# LEDMiniCube_PowerAndAnalog.net
KiCad netlist of a schematic drawn in Altium Designer
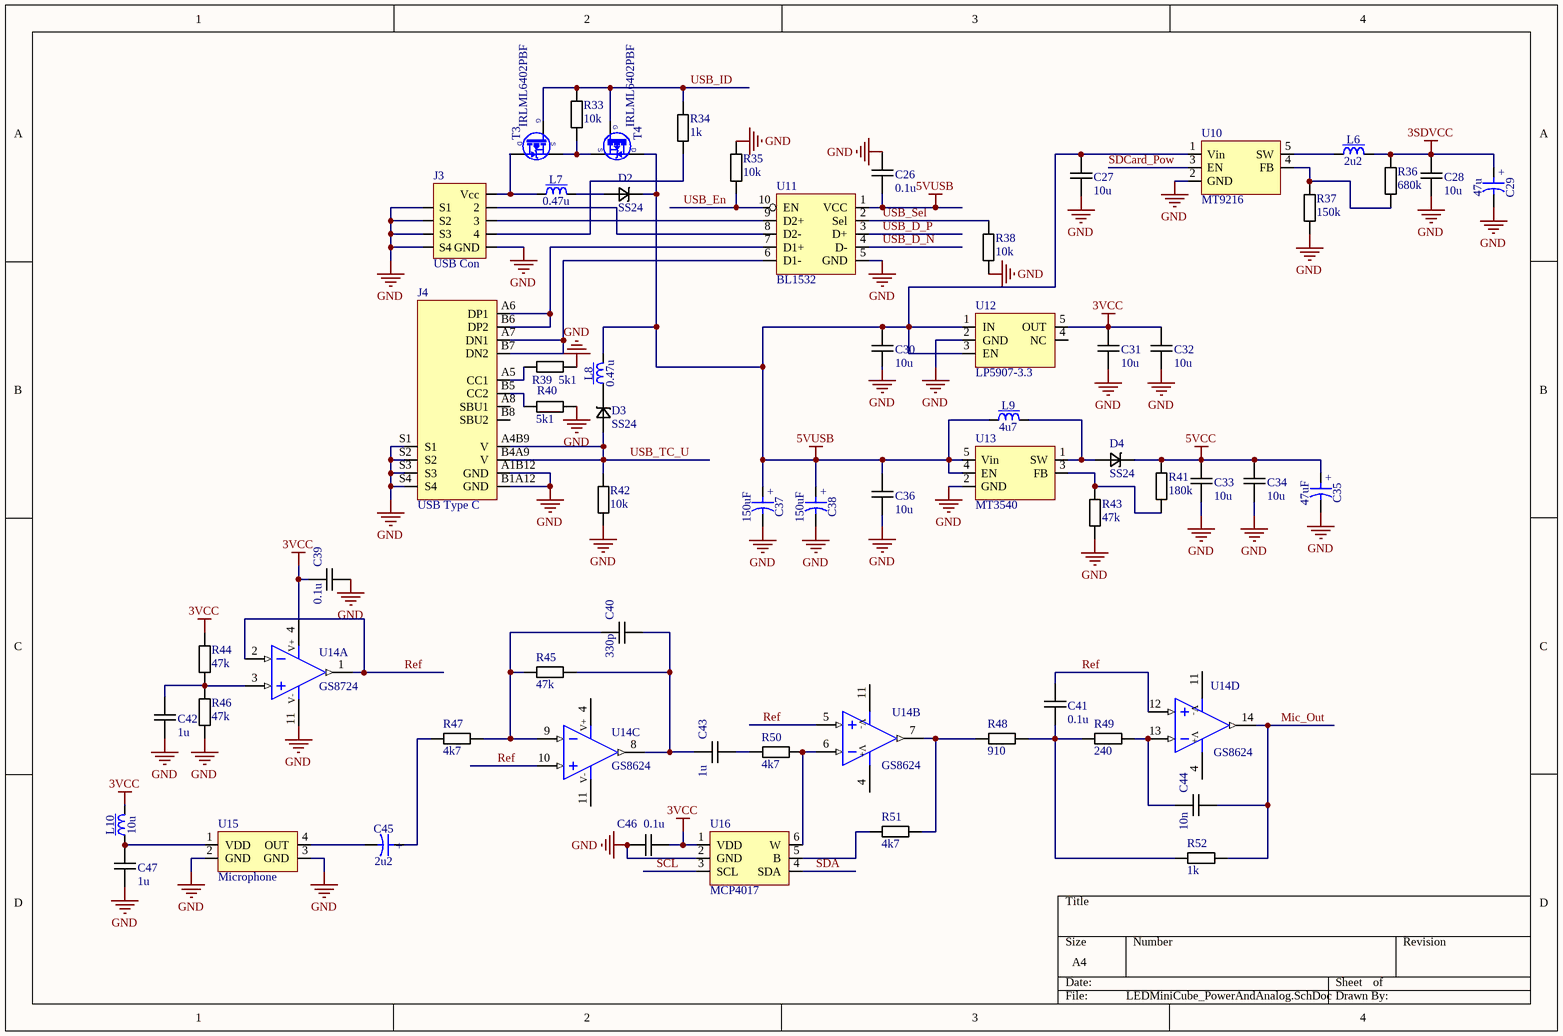
[diagram p0: LEDMiniCube_PowerAndAnalog.SchDoc]

(export (version "E")
  (design (tool "Eeschema 10.0.6"))
  (components
    (comp (ref "C26") (value "0.1u") (footprint "CAPC1608L") (libsource (lib "BMFT_lib") (part "Capacitor")))
    (comp (ref "C27") (value "10u") (footprint "CAPC2012L") (libsource (lib "BMFT_lib") (part "Capacitor")))
    (comp (ref "C28") (value "10u") (footprint "CAPC2012L") (libsource (lib "BMFT_lib") (part "Capacitor")))
    (comp (ref "C29")
      (value "47u")
      (footprint "CAPMP3216X180N")
      (description "Polarised capacitor")
      (fields
        (field (name "PART NUMBER") "CTE3216-18_100UF_6.3V_20%_ESR0500_AVX_TLJ")
        (field (name "VOLTAGE") "6.3V")
        (field (name "AUTHOR") "CERN DEM JLC")
      )
      (libsource (lib "Capacitors") (part "Capacitor - polarized"))
    )
    (comp (ref "C30") (value "10u") (footprint "CAPC2012L") (libsource (lib "BMFT_lib") (part "Capacitor")))
    (comp (ref "C31") (value "10u") (footprint "CAPC2012L") (libsource (lib "BMFT_lib") (part "Capacitor")))
    (comp (ref "C32") (value "10u") (footprint "CAPC2012L") (libsource (lib "BMFT_lib") (part "Capacitor")))
    (comp (ref "C33") (value "10u") (footprint "CAPC3216L") (libsource (lib "BMFT_lib") (part "Capacitor")))
    (comp (ref "C34") (value "10u") (footprint "CAPC3216L") (libsource (lib "BMFT_lib") (part "Capacitor")))
    (comp (ref "C35")
      (value "47uF")
      (footprint "CAPMP3528X120N")
      (description "Polarised capacitor")
      (fields (field (name "VOLTAGE") "10V") (field (name "AUTHOR") "CERN DEM JLC"))
      (libsource (lib "Capacitors") (part "Capacitor - polarized"))
    )
    (comp (ref "C36") (value "10u") (footprint "CAPC2012L") (libsource (lib "BMFT_lib") (part "Capacitor")))
    (comp (ref "C37")
      (value "150uF")
      (footprint "CAPMP7343X200N")
      (description "Polarised capacitor")
      (fields (field (name "VOLTAGE") "6.3V") (field (name "AUTHOR") "CERN DEM JLC"))
      (libsource (lib "Capacitors") (part "Capacitor - polarized"))
    )
    (comp (ref "C38")
      (value "150uF")
      (footprint "CAPMP7343X200N")
      (description "Polarised capacitor")
      (fields (field (name "VOLTAGE") "6.3V") (field (name "AUTHOR") "CERN DEM JLC"))
      (libsource (lib "Capacitors") (part "Capacitor - polarized"))
    )
    (comp (ref "C39") (value "0.1u") (footprint "CAPC1608L") (libsource (lib "BMFT_lib") (part "Capacitor")))
    (comp (ref "C40") (value "330p") (footprint "CAPC1608L") (libsource (lib "BMFT_lib") (part "Capacitor")))
    (comp (ref "C41") (value "0.1u") (footprint "CAPC1608L") (libsource (lib "BMFT_lib") (part "Capacitor")))
    (comp (ref "C42") (value "1u") (footprint "CAPC1608L") (libsource (lib "BMFT_lib") (part "Capacitor")))
    (comp (ref "C43") (value "1u") (footprint "CAPC2012L") (libsource (lib "BMFT_lib") (part "Capacitor")))
    (comp (ref "C44") (value "10n") (footprint "CAPC1608L") (libsource (lib "BMFT_lib") (part "Capacitor")))
    (comp (ref "C45")
      (value "2u2")
      (footprint "CAPMP3216X180N")
      (description "Polarised capacitor")
      (fields
        (field (name "PART NUMBER") "CTE3216-18_100UF_6.3V_20%_ESR0500_AVX_TLJ")
        (field (name "VOLTAGE") "6.3V")
        (field (name "AUTHOR") "CERN DEM JLC")
      )
      (libsource (lib "") (part "Capacitor - polarized_1"))
    )
    (comp (ref "C46") (value "0.1u") (footprint "CAPC1608L") (libsource (lib "BMFT_lib") (part "Capacitor")))
    (comp (ref "C47") (value "1u") (footprint "CAPC1608L") (libsource (lib "BMFT_lib") (part "Capacitor")))
    (comp (ref "D2") (value "SS24") (footprint "SOD-123F") (libsource (lib "BMFT_lib") (part "Schotky")))
    (comp (ref "D3") (value "SS24") (footprint "SOD-123F") (libsource (lib "BMFT_lib") (part "Schotky")))
    (comp (ref "D4") (value "SS24") (footprint "SOD-123F") (libsource (lib "BMFT_lib") (part "Schotky")))
    (comp (ref "J3") (value "USB Con") (footprint "ZX62D") (libsource (lib "BMFT_lib") (part "USB")))
    (comp (ref "J4")
      (value "USB Type C")
      (footprint "U262-161N-4BVC11")
      (fields (field (name "PART") "U262-161N-4BVC11"))
      (libsource (lib "DAC_lib") (part "USB_TypeC"))
    )
    (comp (ref "L6")
      (value "2u2")
      (footprint "IND_COILCRAFT_1206CS")
      (description "Inductor With Core")
      (fields (field (name "AUTHOR") "CERN DEM JLC"))
      (libsource (lib "") (part "Inductor With Magnetic core_1"))
    )
    (comp (ref "L7")
      (value "0.47u")
      (footprint "IND_COILCRAFT_0805CS")
      (description "Inductor With Core")
      (fields (field (name "AUTHOR") "CERN DEM JLC"))
      (libsource (lib "") (part "Inductor With Magnetic core_1"))
    )
    (comp (ref "L8")
      (value "0.47u")
      (footprint "IND_COILCRAFT_0805CS")
      (description "Inductor With Core")
      (fields (field (name "AUTHOR") "CERN DEM JLC"))
      (libsource (lib "Inductors & Transformers") (part "Inductor With Magnetic core"))
    )
    (comp (ref "L9")
      (value "4u7")
      (footprint "IND_COILCRAFT_1206CS")
      (description "Inductor With Core")
      (fields (field (name "AUTHOR") "CERN DEM JLC"))
      (libsource (lib "") (part "Inductor With Magnetic core_1"))
    )
    (comp (ref "L10")
      (value "10u")
      (footprint "INDC2012L")
      (description "Inductor With Core")
      (fields (field (name "AUTHOR") "CERN DEM JLC"))
      (libsource (lib "Inductors & Transformers") (part "Inductor With Magnetic core"))
    )
    (comp (ref "R33") (value "10k") (footprint "RESC1608L") (libsource (lib "BMFT_lib") (part "Resistor")))
    (comp (ref "R34") (value "1k") (footprint "RESC1608L") (libsource (lib "BMFT_lib") (part "Resistor")))
    (comp (ref "R35") (value "10k") (footprint "RESC1608L") (libsource (lib "BMFT_lib") (part "Resistor")))
    (comp (ref "R36") (value "680k") (footprint "RESC1608L") (libsource (lib "BMFT_lib") (part "Resistor")))
    (comp (ref "R37") (value "150k") (footprint "RESC1608L") (libsource (lib "BMFT_lib") (part "Resistor")))
    (comp (ref "R38") (value "10k") (footprint "RESC1608L") (libsource (lib "BMFT_lib") (part "Resistor")))
    (comp (ref "R39") (value "5k1") (footprint "RESC1608L") (libsource (lib "BMFT_lib") (part "Resistor")))
    (comp (ref "R40") (value "5k1") (footprint "RESC1608L") (libsource (lib "BMFT_lib") (part "Resistor")))
    (comp (ref "R41") (value "180k") (footprint "RESC1608L") (libsource (lib "BMFT_lib") (part "Resistor")))
    (comp (ref "R42") (value "10k") (footprint "RESC1608L") (libsource (lib "BMFT_lib") (part "Resistor")))
    (comp (ref "R43") (value "47k") (footprint "RESC1608L") (libsource (lib "BMFT_lib") (part "Resistor")))
    (comp (ref "R44") (value "47k") (footprint "RESC1608L") (libsource (lib "BMFT_lib") (part "Resistor")))
    (comp (ref "R45") (value "47k") (footprint "RESC1608L") (libsource (lib "BMFT_lib") (part "Resistor")))
    (comp (ref "R46") (value "47k") (footprint "RESC1608L") (libsource (lib "BMFT_lib") (part "Resistor")))
    (comp (ref "R47") (value "4k7") (footprint "RESC1608L") (libsource (lib "BMFT_lib") (part "Resistor")))
    (comp (ref "R48") (value "910") (footprint "RESC1608L") (libsource (lib "BMFT_lib") (part "Resistor")))
    (comp (ref "R49") (value "240") (footprint "RESC1608L") (libsource (lib "BMFT_lib") (part "Resistor")))
    (comp (ref "R50") (value "4k7") (footprint "RESC1608L") (libsource (lib "BMFT_lib") (part "Resistor")))
    (comp (ref "R51") (value "4k7") (footprint "RESC1608L") (libsource (lib "BMFT_lib") (part "Resistor")))
    (comp (ref "R52") (value "1k") (footprint "RESC1608L") (libsource (lib "BMFT_lib") (part "Resistor")))
    (comp (ref "T3")
      (value "IRLML6402PBF")
      (footprint "SOT95P237X112-3N")
      (description "P-CHANNEL MOSFET WITH ZENER DIODE")
      (fields (field (name "AUTHOR") "CERN DEM JLC"))
      (libsource (lib "ICs And Semiconductors") (part "P-MOSFET-DZ 1G 2S 3D"))
    )
    (comp (ref "T4")
      (value "IRLML6402PBF")
      (footprint "SOT95P237X112-3N")
      (description "P-CHANNEL MOSFET WITH ZENER DIODE")
      (fields (field (name "AUTHOR") "CERN DEM JLC"))
      (libsource (lib "") (part "P-MOSFET-DZ 1G 2S 3D_1"))
    )
    (comp (ref "U10") (value "MT9216") (footprint "SOT23-5AL") (libsource (lib "BMFT_lib") (part "LM3671")))
    (comp (ref "U11")
      (value "BL1532")
      (footprint "TSSOP50P490X110-10N")
      (libsource (lib "BMFT_lib") (part "BL1532"))
    )
    (comp (ref "U12")
      (value "LP5907-3.3")
      (footprint "SOT95P280X145-5M")
      (fields (field (name "PART") "LP5907MFX-3.3/NOPB"))
      (libsource (lib "DAC_lib") (part "TLV70233"))
    )
    (comp (ref "U13") (value "MT3540") (footprint "SOT23-5AL") (libsource (lib "BMFT_lib") (part "TPS6104x")))
    (comp (ref "U14")
      (value "GS8724")
      (footprint "SOP65P640X120-14N")
      (description "Quad Operational Amplifier")
      (fields (field (name "PART NUMBER") "GS8624-TR") (field (name "AUTHOR") "CERN DEM JLC"))
      (libsource (lib "ICs And Semiconductors") (part "Operational Amplifier x4 Type1"))
    )
    (comp (ref "U15")
      (value "Microphone")
      (footprint "Microphone 3.76x2.95")
      (libsource (lib "BMFT_lib") (part "Microphone MEMS"))
    )
    (comp (ref "U16")
      (value "MCP4017")
      (footprint "SOT65P210X110-6M")
      (libsource (lib "BMFT_lib") (part "MCP4017"))
    )
  )
  (nets
    (net (code "1") (name "/Mic_Out") (class "Default")
      (node (ref "C44") (pin "2") (pintype "passive"))
      (node (ref "R52") (pin "2") (pintype "passive"))
      (node (ref "U14") (pin "14") (pinfunction "OUT_14") (pintype "output"))
    )
    (net (code "2") (name "/Ref") (class "Default")
      (node (ref "C41") (pin "2") (pintype "passive"))
      (node (ref "U14") (pin "1") (pinfunction "OUT_1") (pintype "output"))
      (node (ref "U14") (pin "10") (pinfunction "IN+_10") (pintype "input"))
      (node (ref "U14") (pin "12") (pinfunction "IN+_12") (pintype "input"))
      (node (ref "U14") (pin "2") (pinfunction "IN-_2") (pintype "input"))
      (node (ref "U14") (pin "5") (pinfunction "IN+_5") (pintype "input"))
    )
    (net (code "3") (name "/SCL") (class "Default")
      (node (ref "U16") (pin "3") (pinfunction "SCL_3") (pintype "passive"))
    )
    (net (code "4") (name "/SDA") (class "Default")
      (node (ref "U16") (pin "4") (pinfunction "SDA_4") (pintype "passive"))
    )
    (net (code "5") (name "/SDCard_Pow") (class "Default")
      (node (ref "U10") (pin "3") (pinfunction "EN_3") (pintype "passive"))
    )
    (net (code "6") (name "/USB_D_N") (class "Default")
      (node (ref "U11") (pin "4") (pinfunction "D-_4") (pintype "passive"))
    )
    (net (code "7") (name "/USB_D_P") (class "Default")
      (node (ref "U11") (pin "3") (pinfunction "D+_3") (pintype "passive"))
    )
    (net (code "8") (name "/USB_En") (class "Default")
      (node (ref "R35") (pin "1") (pintype "passive"))
      (node (ref "U11") (pin "10") (pinfunction "EN_10") (pintype "passive"))
    )
    (net (code "9") (name "/USB_ID") (class "Default")
      (node (ref "R33") (pin "2") (pintype "passive"))
      (node (ref "R34") (pin "2") (pintype "passive"))
      (node (ref "T3") (pin "1") (pinfunction "G_1") (pintype "passive"))
      (node (ref "T4") (pin "1") (pinfunction "G_1") (pintype "passive"))
    )
    (net (code "10") (name "/USB_Sel") (class "Default")
      (node (ref "R38") (pin "2") (pintype "passive"))
      (node (ref "U11") (pin "2") (pinfunction "Sel_2") (pintype "passive"))
    )
    (net (code "11") (name "/USB_TC_U") (class "Default")
      (node (ref "D3") (pin "1") (pintype "passive"))
      (node (ref "J4") (pin "A4B9") (pinfunction "V_A4B9") (pintype "passive"))
      (node (ref "J4") (pin "B4A9") (pinfunction "V_B4A9") (pintype "passive"))
      (node (ref "R42") (pin "2") (pintype "passive"))
    )
    (net (code "12") (name "3SDVCC") (class "Default")
      (node (ref "C28") (pin "2") (pintype "passive"))
      (node (ref "C29") (pin "1") (pinfunction "1_1") (pintype "passive"))
      (node (ref "L6") (pin "2") (pinfunction "2_2") (pintype "passive"))
      (node (ref "R36") (pin "2") (pintype "passive"))
    )
    (net (code "13") (name "3VCC") (class "Default")
      (node (ref "C31") (pin "2") (pintype "passive"))
      (node (ref "C32") (pin "2") (pintype "passive"))
      (node (ref "C39") (pin "1") (pintype "passive"))
      (node (ref "C46") (pin "2") (pintype "passive"))
      (node (ref "L10") (pin "2") (pinfunction "2_2") (pintype "passive"))
      (node (ref "R44") (pin "2") (pintype "passive"))
      (node (ref "U12") (pin "5") (pinfunction "OUT_5") (pintype "passive"))
      (node (ref "U14") (pin "4") (pinfunction "V+_4") (pintype "power_in"))
      (node (ref "U16") (pin "1") (pinfunction "VDD_1") (pintype "passive"))
    )
    (net (code "14") (name "5VCC") (class "Default")
      (node (ref "C33") (pin "2") (pintype "passive"))
      (node (ref "C34") (pin "2") (pintype "passive"))
      (node (ref "C35") (pin "1") (pinfunction "1_1") (pintype "passive"))
      (node (ref "D4") (pin "2") (pintype "passive"))
      (node (ref "R41") (pin "2") (pintype "passive"))
    )
    (net (code "15") (name "5VUSB") (class "Default")
      (node (ref "C26") (pin "1") (pintype "passive"))
      (node (ref "C27") (pin "2") (pintype "passive"))
      (node (ref "C30") (pin "2") (pintype "passive"))
      (node (ref "C36") (pin "2") (pintype "passive"))
      (node (ref "C37") (pin "1") (pinfunction "1_1") (pintype "passive"))
      (node (ref "C38") (pin "1") (pinfunction "1_1") (pintype "passive"))
      (node (ref "D2") (pin "2") (pintype "passive"))
      (node (ref "L8") (pin "2") (pinfunction "2_2") (pintype "passive"))
      (node (ref "L9") (pin "1") (pinfunction "1_1") (pintype "passive"))
      (node (ref "T4") (pin "3") (pinfunction "D_3") (pintype "passive"))
      (node (ref "U10") (pin "1") (pinfunction "Vin_1") (pintype "power_in"))
      (node (ref "U11") (pin "1") (pinfunction "VCC_1") (pintype "passive"))
      (node (ref "U12") (pin "1") (pinfunction "IN_1") (pintype "passive"))
      (node (ref "U12") (pin "3") (pinfunction "EN_3") (pintype "passive"))
      (node (ref "U13") (pin "4") (pinfunction "EN_4") (pintype "passive"))
      (node (ref "U13") (pin "5") (pinfunction "Vin_5") (pintype "power_in"))
    )
    (net (code "16") (name "GND") (class "Default")
      (node (ref "C26") (pin "2") (pintype "passive"))
      (node (ref "C27") (pin "1") (pintype "passive"))
      (node (ref "C28") (pin "1") (pintype "passive"))
      (node (ref "C29") (pin "2") (pinfunction "2_2") (pintype "passive"))
      (node (ref "C30") (pin "1") (pintype "passive"))
      (node (ref "C31") (pin "1") (pintype "passive"))
      (node (ref "C32") (pin "1") (pintype "passive"))
      (node (ref "C33") (pin "1") (pintype "passive"))
      (node (ref "C34") (pin "1") (pintype "passive"))
      (node (ref "C35") (pin "2") (pinfunction "2_2") (pintype "passive"))
      (node (ref "C36") (pin "1") (pintype "passive"))
      (node (ref "C37") (pin "2") (pinfunction "2_2") (pintype "passive"))
      (node (ref "C38") (pin "2") (pinfunction "2_2") (pintype "passive"))
      (node (ref "C39") (pin "2") (pintype "passive"))
      (node (ref "C42") (pin "1") (pintype "passive"))
      (node (ref "C46") (pin "1") (pintype "passive"))
      (node (ref "C47") (pin "1") (pintype "passive"))
      (node (ref "J3") (pin "5") (pinfunction "GND_5") (pintype "power_in"))
      (node (ref "J3") (pin "S1") (pinfunction "S1_S1") (pintype "passive"))
      (node (ref "J3") (pin "S2") (pinfunction "S2_S2") (pintype "passive"))
      (node (ref "J3") (pin "S3") (pinfunction "S3_S3") (pintype "passive"))
      (node (ref "J3") (pin "S4") (pinfunction "S4_S4") (pintype "passive"))
      (node (ref "J4") (pin "A1B12") (pinfunction "GND_A1B12") (pintype "passive"))
      (node (ref "J4") (pin "B1A12") (pinfunction "GND_B1A12") (pintype "passive"))
      (node (ref "J4") (pin "S1") (pinfunction "S1_S1") (pintype "passive"))
      (node (ref "J4") (pin "S2") (pinfunction "S2_S2") (pintype "passive"))
      (node (ref "J4") (pin "S3") (pinfunction "S3_S3") (pintype "passive"))
      (node (ref "J4") (pin "S4") (pinfunction "S4_S4") (pintype "passive"))
      (node (ref "R35") (pin "2") (pintype "passive"))
      (node (ref "R37") (pin "1") (pintype "passive"))
      (node (ref "R38") (pin "1") (pintype "passive"))
      (node (ref "R39") (pin "2") (pintype "passive"))
      (node (ref "R40") (pin "2") (pintype "passive"))
      (node (ref "R42") (pin "1") (pintype "passive"))
      (node (ref "R43") (pin "1") (pintype "passive"))
      (node (ref "R46") (pin "1") (pintype "passive"))
      (node (ref "U10") (pin "2") (pinfunction "GND_2") (pintype "power_in"))
      (node (ref "U11") (pin "5") (pinfunction "GND_5") (pintype "passive"))
      (node (ref "U12") (pin "2") (pinfunction "GND_2") (pintype "passive"))
      (node (ref "U13") (pin "2") (pinfunction "GND_2") (pintype "power_in"))
      (node (ref "U14") (pin "11") (pinfunction "V-_11") (pintype "power_in"))
      (node (ref "U15") (pin "2") (pinfunction "GND_2") (pintype "passive"))
      (node (ref "U15") (pin "3") (pinfunction "GND_3") (pintype "passive"))
      (node (ref "U16") (pin "2") (pinfunction "GND_2") (pintype "passive"))
    )
    (net (code "17") (name "Net-(C41-Pad1)") (class "Default")
      (node (ref "C41") (pin "1") (pintype "passive"))
      (node (ref "R48") (pin "2") (pintype "passive"))
      (node (ref "R49") (pin "1") (pintype "passive"))
      (node (ref "R52") (pin "1") (pintype "passive"))
    )
    (net (code "18") (name "Net-(C43-Pad2)") (class "Default")
      (node (ref "C43") (pin "2") (pintype "passive"))
      (node (ref "R50") (pin "1") (pintype "passive"))
    )
    (net (code "19") (name "Net-(C45-Pad1)") (class "Default")
      (node (ref "C45") (pin "1") (pinfunction "1_1") (pintype "passive"))
      (node (ref "R47") (pin "1") (pintype "passive"))
    )
    (net (code "20") (name "Net-(D2-Pad1)") (class "Default")
      (node (ref "D2") (pin "1") (pintype "passive"))
      (node (ref "L7") (pin "2") (pinfunction "2_2") (pintype "passive"))
    )
    (net (code "21") (name "Net-(D3-Pad2)") (class "Default")
      (node (ref "D3") (pin "2") (pintype "passive"))
      (node (ref "L8") (pin "1") (pinfunction "1_1") (pintype "passive"))
    )
    (net (code "22") (name "Net-(J3-Pad4)") (class "Default")
      (node (ref "J3") (pin "4") (pinfunction "4_4") (pintype "passive"))
      (node (ref "R34") (pin "1") (pintype "passive"))
    )
    (net (code "23") (name "Net-(J3-Vcc)") (class "Default")
      (node (ref "J3") (pin "1") (pinfunction "Vcc_1") (pintype "power_in"))
      (node (ref "L7") (pin "1") (pinfunction "1_1") (pintype "passive"))
      (node (ref "T3") (pin "3") (pinfunction "D_3") (pintype "passive"))
    )
    (net (code "24") (name "Net-(J4-CC1)") (class "Default")
      (node (ref "J4") (pin "A5") (pinfunction "CC1_A5") (pintype "passive"))
      (node (ref "R39") (pin "1") (pintype "passive"))
    )
    (net (code "25") (name "Net-(J4-CC2)") (class "Default")
      (node (ref "J4") (pin "B5") (pinfunction "CC2_B5") (pintype "passive"))
      (node (ref "R40") (pin "1") (pintype "passive"))
    )
    (net (code "26") (name "Net-(J4-DN1)") (class "Default")
      (node (ref "J4") (pin "A7") (pinfunction "DN1_A7") (pintype "passive"))
      (node (ref "J4") (pin "B7") (pinfunction "DN2_B7") (pintype "passive"))
      (node (ref "U11") (pin "6") (pinfunction "D1-_6") (pintype "passive"))
    )
    (net (code "27") (name "Net-(J4-DP1)") (class "Default")
      (node (ref "J4") (pin "A6") (pinfunction "DP1_A6") (pintype "passive"))
      (node (ref "J4") (pin "B6") (pinfunction "DP2_B6") (pintype "passive"))
      (node (ref "U11") (pin "7") (pinfunction "D1+_7") (pintype "passive"))
    )
    (net (code "28") (name "Net-(T3-S)") (class "Default")
      (node (ref "R33") (pin "1") (pintype "passive"))
      (node (ref "T3") (pin "2") (pinfunction "S_2") (pintype "passive"))
      (node (ref "T4") (pin "2") (pinfunction "S_2") (pintype "passive"))
    )
    (net (code "29") (name "Net-(U10-FB)") (class "Default")
      (node (ref "R36") (pin "1") (pintype "passive"))
      (node (ref "R37") (pin "2") (pintype "passive"))
      (node (ref "U10") (pin "4") (pinfunction "FB_4") (pintype "passive"))
    )
    (net (code "30") (name "Net-(U10-SW)") (class "Default")
      (node (ref "L6") (pin "1") (pinfunction "1_1") (pintype "passive"))
      (node (ref "U10") (pin "5") (pinfunction "SW_5") (pintype "power_in"))
    )
    (net (code "31") (name "Net-(U11-D2+)") (class "Default")
      (node (ref "J3") (pin "3") (pinfunction "3_3") (pintype "passive"))
      (node (ref "U11") (pin "9") (pinfunction "D2+_9") (pintype "passive"))
    )
    (net (code "32") (name "Net-(U11-D2-)") (class "Default")
      (node (ref "J3") (pin "2") (pinfunction "2_2") (pintype "passive"))
      (node (ref "U11") (pin "8") (pinfunction "D2-_8") (pintype "passive"))
    )
    (net (code "33") (name "Net-(U13-FB)") (class "Default")
      (node (ref "R41") (pin "1") (pintype "passive"))
      (node (ref "R43") (pin "2") (pintype "passive"))
      (node (ref "U13") (pin "3") (pinfunction "FB_3") (pintype "passive"))
    )
    (net (code "34") (name "Net-(U13-SW)") (class "Default")
      (node (ref "D4") (pin "1") (pintype "passive"))
      (node (ref "L9") (pin "2") (pinfunction "2_2") (pintype "passive"))
      (node (ref "U13") (pin "1") (pinfunction "SW_1") (pintype "power_in"))
    )
    (net (code "35") (name "Net-(U14A-IN+)") (class "Default")
      (node (ref "C42") (pin "2") (pintype "passive"))
      (node (ref "R44") (pin "1") (pintype "passive"))
      (node (ref "R46") (pin "2") (pintype "passive"))
      (node (ref "U14") (pin "3") (pinfunction "IN+_3") (pintype "input"))
    )
    (net (code "36") (name "Net-(U14B-IN-)") (class "Default")
      (node (ref "R50") (pin "2") (pintype "passive"))
      (node (ref "U14") (pin "6") (pinfunction "IN-_6") (pintype "input"))
      (node (ref "U16") (pin "6") (pinfunction "W_6") (pintype "passive"))
    )
    (net (code "37") (name "Net-(U14B-OUT)") (class "Default")
      (node (ref "R48") (pin "1") (pintype "passive"))
      (node (ref "R51") (pin "2") (pintype "passive"))
      (node (ref "U14") (pin "7") (pinfunction "OUT_7") (pintype "output"))
    )
    (net (code "38") (name "Net-(U14C-IN-)") (class "Default")
      (node (ref "C40") (pin "1") (pintype "passive"))
      (node (ref "R45") (pin "1") (pintype "passive"))
      (node (ref "R47") (pin "2") (pintype "passive"))
      (node (ref "U14") (pin "9") (pinfunction "IN-_9") (pintype "input"))
    )
    (net (code "39") (name "Net-(U14C-OUT)") (class "Default")
      (node (ref "C40") (pin "2") (pintype "passive"))
      (node (ref "C43") (pin "1") (pintype "passive"))
      (node (ref "R45") (pin "2") (pintype "passive"))
      (node (ref "U14") (pin "8") (pinfunction "OUT_8") (pintype "output"))
    )
    (net (code "40") (name "Net-(U14D-IN-)") (class "Default")
      (node (ref "C44") (pin "1") (pintype "passive"))
      (node (ref "R49") (pin "2") (pintype "passive"))
      (node (ref "U14") (pin "13") (pinfunction "IN-_13") (pintype "input"))
    )
    (net (code "41") (name "Net-(U15-OUT)") (class "Default")
      (node (ref "C45") (pin "2") (pinfunction "2_2") (pintype "passive"))
      (node (ref "U15") (pin "4") (pinfunction "OUT_4") (pintype "passive"))
    )
    (net (code "42") (name "Net-(U15-VDD)") (class "Default")
      (node (ref "C47") (pin "2") (pintype "passive"))
      (node (ref "L10") (pin "1") (pinfunction "1_1") (pintype "passive"))
      (node (ref "U15") (pin "1") (pinfunction "VDD_1") (pintype "passive"))
    )
    (net (code "43") (name "Net-(U16-B)") (class "Default")
      (node (ref "R51") (pin "1") (pintype "passive"))
      (node (ref "U16") (pin "5") (pinfunction "B_5") (pintype "passive"))
    )
    (net (code "44") (name "unconnected-(J4-SBU1-PadA8)") (class "Default")
      (node (ref "J4") (pin "A8") (pinfunction "SBU1_A8") (pintype "passive"))
    )
    (net (code "45") (name "unconnected-(J4-SBU2-PadB8)") (class "Default")
      (node (ref "J4") (pin "B8") (pinfunction "SBU2_B8") (pintype "passive"))
    )
    (net (code "46") (name "unconnected-(U12-NC-Pad4)") (class "Default")
      (node (ref "U12") (pin "4") (pinfunction "NC_4") (pintype "passive"))
    )
    (net (code "47") (name "unconnected-(U14B-V+-Pad4)") (class "Default")
      (node (ref "U14") (pin "4") (pinfunction "V+_4") (pintype "power_in"))
    )
    (net (code "48") (name "unconnected-(U14B-V--Pad11)") (class "Default")
      (node (ref "U14") (pin "11") (pinfunction "V-_11") (pintype "power_in"))
    )
    (net (code "49") (name "unconnected-(U14C-V+-Pad4)") (class "Default")
      (node (ref "U14") (pin "4") (pinfunction "V+_4") (pintype "power_in"))
    )
    (net (code "50") (name "unconnected-(U14C-V--Pad11)") (class "Default")
      (node (ref "U14") (pin "11") (pinfunction "V-_11") (pintype "power_in"))
    )
    (net (code "51") (name "unconnected-(U14D-V+-Pad4)") (class "Default")
      (node (ref "U14") (pin "4") (pinfunction "V+_4") (pintype "power_in"))
    )
    (net (code "52") (name "unconnected-(U14D-V--Pad11)") (class "Default")
      (node (ref "U14") (pin "11") (pinfunction "V-_11") (pintype "power_in"))
    )
  )
)
